# Voltage_Sensing.net
KiCad netlist of a schematic drawn in Altium Designer
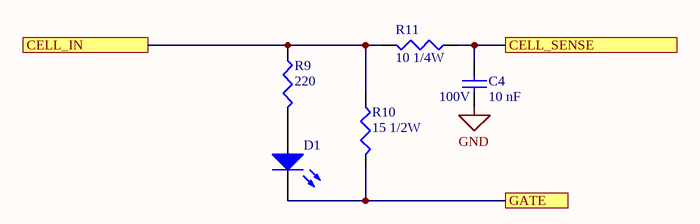
[diagram p0: Voltage Sensing.SchDoc]

(export (version "E")
  (design (tool "Eeschema 10.0.6"))
  (components
    (comp (ref "C4")
      (value "100V")
      (footprint "6-0805_N")
      (description "Capacitor")
      (fields (field (name "ALTIUM_VALUE") "10 nF") (field (name "PUBLISHER") "Altium Limited"))
      (libsource (lib "Miscellaneous Devices") (part "Cap"))
    )
    (comp (ref "D1")
      (value "LED2")
      (footprint "DIOC1608X06N")
      (description "Green LED")
      (fields (field (name "PUBLISHER") "Altium Limited"))
      (libsource (lib "Miscellaneous Devices") (part "LED2"))
    )
    (comp (ref "R9")
      (value "220")
      (footprint "J1-0603")
      (description "Resistor")
      (fields (field (name "Comment") "Res3") (field (name "PUBLISHER") "Altium Limited"))
      (libsource (lib "Miscellaneous Devices") (part "Res3"))
    )
    (comp (ref "R10")
      (value "15 1/2W")
      (footprint "14-1210")
      (description "Resistor")
      (fields (field (name "Comment") "Res3") (field (name "PUBLISHER") "Altium Limited"))
      (libsource (lib "Miscellaneous Devices") (part "Res3"))
    )
    (comp (ref "R11")
      (value "10 1/4W")
      (footprint "C1206")
      (description "Resistor")
      (fields (field (name "PUBLISHER") "Altium Limited"))
      (libsource (lib "Miscellaneous Devices") (part "Res3"))
    )
  )
  (nets
    (net (code "1") (name "/CELL_IN") (class "Default")
      (node (ref "R10") (pin "1") (pinfunction "1_1") (pintype "passive"))
      (node (ref "R11") (pin "2") (pinfunction "2_2") (pintype "passive"))
      (node (ref "R9") (pin "1") (pinfunction "1_1") (pintype "passive"))
    )
    (net (code "2") (name "/CELL_SENSE") (class "Default")
      (node (ref "C4") (pin "2") (pinfunction "2_2") (pintype "passive"))
      (node (ref "R11") (pin "1") (pinfunction "1_1") (pintype "passive"))
    )
    (net (code "3") (name "/GATE") (class "Default")
      (node (ref "D1") (pin "2") (pinfunction "K_2") (pintype "passive"))
      (node (ref "R10") (pin "2") (pinfunction "2_2") (pintype "passive"))
    )
    (net (code "4") (name "GND") (class "Default")
      (node (ref "C4") (pin "1") (pinfunction "1_1") (pintype "passive"))
    )
    (net (code "5") (name "Net-(D1-A)") (class "Default")
      (node (ref "D1") (pin "1") (pinfunction "A_1") (pintype "passive"))
      (node (ref "R9") (pin "2") (pinfunction "2_2") (pintype "passive"))
    )
  )
)
